# programming.net
KiCad netlist of a schematic drawn in Altium Designer
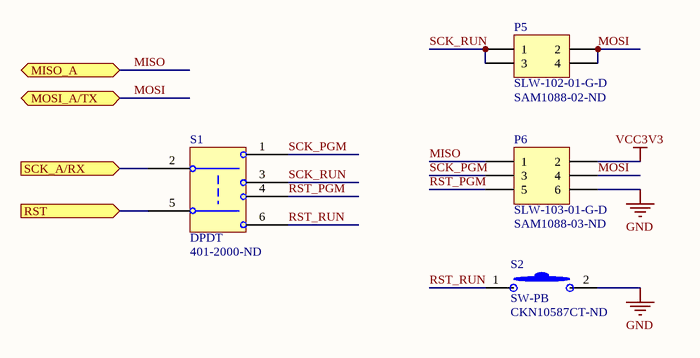
[diagram p0: programming.SchDoc]

(export (version "E")
  (design (tool "Eeschema 10.0.6"))
  (components
    (comp (ref "P5")
      (value "SLW-102-01-G-D")
      (footprint "SLW-102-01-X-D")
      (description "4 pos 100mil pitch low profile header")
      (fields (field (name "SUPPLIER PART NUMBER 1") "SAM1088-02-ND"))
      (libsource (lib "heron-general") (part "SLW-102-01-G-D"))
    )
    (comp (ref "P6")
      (value "SLW-103-01-G-D")
      (footprint "SLW-103-01-X-D")
      (description "6 pos 100mil pitch low profile header")
      (fields (field (name "SUPPLIER PART NUMBER 1") "SAM1088-03-ND"))
      (libsource (lib "heron-general") (part "SLW-103-01-G-D"))
    )
    (comp (ref "S1")
      (value "DPDT")
      (footprint "JS202011AQN - Slide Switch")
      (description "DPDT Switch, customized for the pinout of the JS202011AQN switch.")
      (fields (field (name "SUPPLIER PART NUMBER 1") "401-2000-ND"))
      (libsource (lib "heron-general") (part "DPDT Switch"))
    )
    (comp (ref "S2")
      (value "SW-PB")
      (footprint "PTS830GM140 SMTR LFS - Pushbutton")
      (description "Schematic symbol for a generic 2-pin pushbutton, OFF-mom.")
      (fields (field (name "SUPPLIER PART NUMBER 1") "CKN10587CT-ND"))
      (libsource (lib "heron-general") (part "Pushbutton - Low Profile"))
    )
  )
  (nets
    (net (code "1") (name "/MISO") (class "Default")
      (node (ref "P6") (pin "1") (pinfunction "1_1") (pintype "passive"))
    )
    (net (code "2") (name "/MOSI") (class "Default")
      (node (ref "P5") (pin "2") (pinfunction "2_2") (pintype "passive"))
      (node (ref "P5") (pin "4") (pinfunction "4_4") (pintype "passive"))
      (node (ref "P6") (pin "4") (pinfunction "4_4") (pintype "passive"))
    )
    (net (code "3") (name "/RST") (class "Default")
      (node (ref "S1") (pin "5") (pinfunction "POLE2_5") (pintype "passive"))
    )
    (net (code "4") (name "/RST_PGM") (class "Default")
      (node (ref "P6") (pin "5") (pinfunction "5_5") (pintype "passive"))
      (node (ref "S1") (pin "4") (pinfunction "POLE2A_4") (pintype "passive"))
    )
    (net (code "5") (name "/RST_RUN") (class "Default")
      (node (ref "S1") (pin "6") (pinfunction "POLE2B_6") (pintype "passive"))
      (node (ref "S2") (pin "1") (pinfunction "1_1") (pintype "passive"))
    )
    (net (code "6") (name "/SCK_A{slash}RX") (class "Default")
      (node (ref "S1") (pin "2") (pinfunction "POLE1_2") (pintype "passive"))
    )
    (net (code "7") (name "/SCK_PGM") (class "Default")
      (node (ref "P6") (pin "3") (pinfunction "3_3") (pintype "passive"))
      (node (ref "S1") (pin "1") (pinfunction "POLE1A_1") (pintype "passive"))
    )
    (net (code "8") (name "/SCK_RUN") (class "Default")
      (node (ref "P5") (pin "1") (pinfunction "1_1") (pintype "passive"))
      (node (ref "P5") (pin "3") (pinfunction "3_3") (pintype "passive"))
      (node (ref "S1") (pin "3") (pinfunction "POLE1B_3") (pintype "passive"))
    )
    (net (code "9") (name "GND") (class "Default")
      (node (ref "P6") (pin "6") (pinfunction "6_6") (pintype "passive"))
      (node (ref "S2") (pin "2") (pinfunction "2_2") (pintype "passive"))
    )
    (net (code "10") (name "VCC3V3") (class "Default")
      (node (ref "P6") (pin "2") (pinfunction "2_2") (pintype "passive"))
    )
  )
)
